# FubarStep_v10thin.net
KiCad netlist of a schematic drawn in EAGLE
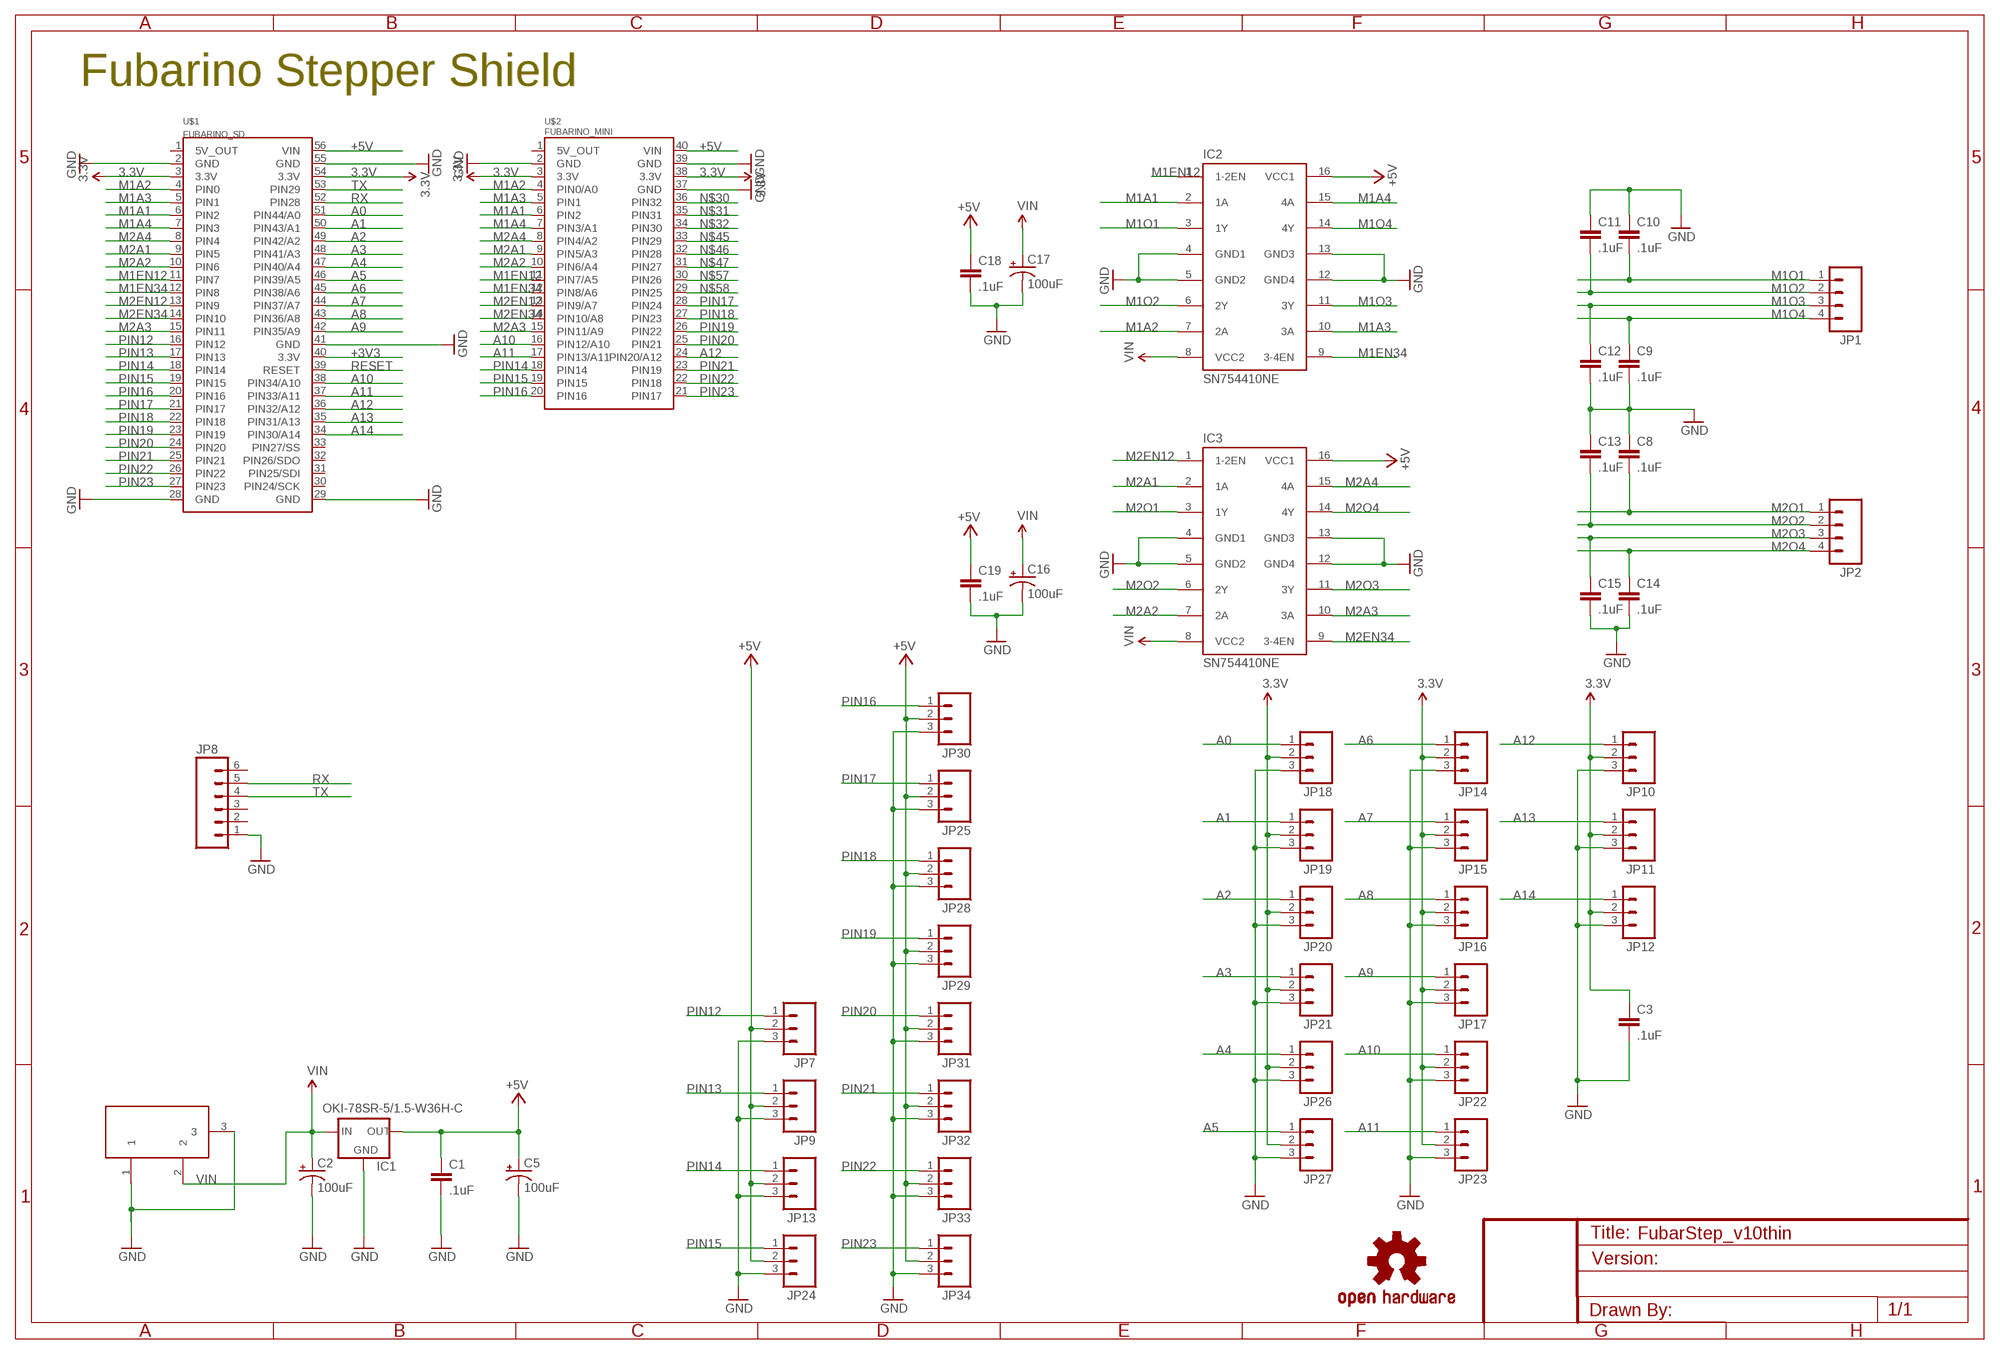
[diagram p0: schematic, sheet 1]

(export (version "E")
  (design (tool "Eeschema 10.0.6"))
  (components
    (comp (ref "C1")
      (value ".1uF")
      (footprint "eagle-import:CAP-PTH-SMALL")
      (libsource (lib "eagle-import") (part "CAPPTH"))
    )
    (comp (ref "C2")
      (value "100uF")
      (footprint "eagle-import:CPOL-RADIAL-100UF-25V")
      (libsource (lib "eagle-import") (part "CAP_POLPTH1"))
    )
    (comp (ref "C3")
      (value ".1uF")
      (footprint "eagle-import:CAP-PTH-SMALL")
      (libsource (lib "eagle-import") (part "CAPPTH"))
    )
    (comp (ref "C5")
      (value "100uF")
      (footprint "eagle-import:CPOL-RADIAL-100UF-25V")
      (libsource (lib "eagle-import") (part "CAP_POLPTH1"))
    )
    (comp (ref "C8")
      (value ".1uF")
      (footprint "eagle-import:CAP-PTH-SMALL")
      (libsource (lib "eagle-import") (part "CAPPTH"))
    )
    (comp (ref "C9")
      (value ".1uF")
      (footprint "eagle-import:CAP-PTH-SMALL")
      (libsource (lib "eagle-import") (part "CAPPTH"))
    )
    (comp (ref "C10")
      (value ".1uF")
      (footprint "eagle-import:CAP-PTH-SMALL")
      (libsource (lib "eagle-import") (part "CAPPTH"))
    )
    (comp (ref "C11")
      (value ".1uF")
      (footprint "eagle-import:CAP-PTH-SMALL")
      (libsource (lib "eagle-import") (part "CAPPTH"))
    )
    (comp (ref "C12")
      (value ".1uF")
      (footprint "eagle-import:CAP-PTH-SMALL")
      (libsource (lib "eagle-import") (part "CAPPTH"))
    )
    (comp (ref "C13")
      (value ".1uF")
      (footprint "eagle-import:CAP-PTH-SMALL")
      (libsource (lib "eagle-import") (part "CAPPTH"))
    )
    (comp (ref "C14")
      (value ".1uF")
      (footprint "eagle-import:CAP-PTH-SMALL")
      (libsource (lib "eagle-import") (part "CAPPTH"))
    )
    (comp (ref "C15")
      (value ".1uF")
      (footprint "eagle-import:CAP-PTH-SMALL")
      (libsource (lib "eagle-import") (part "CAPPTH"))
    )
    (comp (ref "C16")
      (value "100uF")
      (footprint "eagle-import:CPOL-RADIAL-100UF-25V")
      (libsource (lib "eagle-import") (part "CAP_POLPTH1"))
    )
    (comp (ref "C17")
      (value "100uF")
      (footprint "eagle-import:CPOL-RADIAL-100UF-25V")
      (libsource (lib "eagle-import") (part "CAP_POLPTH1"))
    )
    (comp (ref "C18")
      (value ".1uF")
      (footprint "eagle-import:CAP-PTH-SMALL")
      (libsource (lib "eagle-import") (part "CAPPTH"))
    )
    (comp (ref "C19")
      (value ".1uF")
      (footprint "eagle-import:CAP-PTH-SMALL")
      (libsource (lib "eagle-import") (part "CAPPTH"))
    )
    (comp (ref "IC1")
      (value "OKI-78SR-5/1.5-W36H-C")
      (footprint "eagle-import:TO220-IGO")
      (libsource (lib "eagle-import") (part "V_REG_78XXSINK"))
    )
    (comp (ref "IC2")
      (value "SN754410NE")
      (footprint "eagle-import:DIL16")
      (fields (field (name "MF") "Arrow Electronics") (field (name "MPN") "L293E"))
      (libsource (lib "eagle-import") (part "L293E"))
    )
    (comp (ref "IC3")
      (value "SN754410NE")
      (footprint "eagle-import:DIL16")
      (fields (field (name "MF") "Arrow Electronics") (field (name "MPN") "L293E"))
      (libsource (lib "eagle-import") (part "L293E"))
    )
    (comp (ref "JP1")
      (value "M04SCREW_LOCK")
      (footprint "eagle-import:SCREWTERMINAL-3.5MM-4_LOCK")
      (libsource (lib "eagle-import") (part "M04SCREW_LOCK"))
    )
    (comp (ref "JP2")
      (value "M04SCREW_LOCK")
      (footprint "eagle-import:SCREWTERMINAL-3.5MM-4_LOCK")
      (libsource (lib "eagle-import") (part "M04SCREW_LOCK"))
    )
    (comp (ref "JP7")
      (value "M03PTH")
      (footprint "eagle-import:1X03")
      (libsource (lib "eagle-import") (part "M03PTH"))
    )
    (comp (ref "JP8")
      (value "M06LOCK")
      (footprint "eagle-import:1X06_LOCK")
      (libsource (lib "eagle-import") (part "M06LOCK"))
    )
    (comp (ref "JP9")
      (value "M03PTH")
      (footprint "eagle-import:1X03")
      (libsource (lib "eagle-import") (part "M03PTH"))
    )
    (comp (ref "JP10")
      (value "M03PTH")
      (footprint "eagle-import:1X03")
      (libsource (lib "eagle-import") (part "M03PTH"))
    )
    (comp (ref "JP11")
      (value "M03PTH")
      (footprint "eagle-import:1X03")
      (libsource (lib "eagle-import") (part "M03PTH"))
    )
    (comp (ref "JP12")
      (value "M03PTH")
      (footprint "eagle-import:1X03")
      (libsource (lib "eagle-import") (part "M03PTH"))
    )
    (comp (ref "JP13")
      (value "M03PTH")
      (footprint "eagle-import:1X03")
      (libsource (lib "eagle-import") (part "M03PTH"))
    )
    (comp (ref "JP14")
      (value "M03PTH")
      (footprint "eagle-import:1X03")
      (libsource (lib "eagle-import") (part "M03PTH"))
    )
    (comp (ref "JP15")
      (value "M03PTH")
      (footprint "eagle-import:1X03")
      (libsource (lib "eagle-import") (part "M03PTH"))
    )
    (comp (ref "JP16")
      (value "M03PTH")
      (footprint "eagle-import:1X03")
      (libsource (lib "eagle-import") (part "M03PTH"))
    )
    (comp (ref "JP17")
      (value "M03PTH")
      (footprint "eagle-import:1X03")
      (libsource (lib "eagle-import") (part "M03PTH"))
    )
    (comp (ref "JP18")
      (value "M03PTH")
      (footprint "eagle-import:1X03")
      (libsource (lib "eagle-import") (part "M03PTH"))
    )
    (comp (ref "JP19")
      (value "M03PTH")
      (footprint "eagle-import:1X03")
      (libsource (lib "eagle-import") (part "M03PTH"))
    )
    (comp (ref "JP20")
      (value "M03PTH")
      (footprint "eagle-import:1X03")
      (libsource (lib "eagle-import") (part "M03PTH"))
    )
    (comp (ref "JP21")
      (value "M03PTH")
      (footprint "eagle-import:1X03")
      (libsource (lib "eagle-import") (part "M03PTH"))
    )
    (comp (ref "JP22")
      (value "M03PTH")
      (footprint "eagle-import:1X03")
      (libsource (lib "eagle-import") (part "M03PTH"))
    )
    (comp (ref "JP23")
      (value "M03PTH")
      (footprint "eagle-import:1X03")
      (libsource (lib "eagle-import") (part "M03PTH"))
    )
    (comp (ref "JP24")
      (value "M03PTH")
      (footprint "eagle-import:1X03")
      (libsource (lib "eagle-import") (part "M03PTH"))
    )
    (comp (ref "JP25")
      (value "M03PTH")
      (footprint "eagle-import:1X03")
      (libsource (lib "eagle-import") (part "M03PTH"))
    )
    (comp (ref "JP26")
      (value "M03PTH")
      (footprint "eagle-import:1X03")
      (libsource (lib "eagle-import") (part "M03PTH"))
    )
    (comp (ref "JP27")
      (value "M03PTH")
      (footprint "eagle-import:1X03")
      (libsource (lib "eagle-import") (part "M03PTH"))
    )
    (comp (ref "JP28")
      (value "M03PTH")
      (footprint "eagle-import:1X03")
      (libsource (lib "eagle-import") (part "M03PTH"))
    )
    (comp (ref "JP29")
      (value "M03PTH")
      (footprint "eagle-import:1X03")
      (libsource (lib "eagle-import") (part "M03PTH"))
    )
    (comp (ref "JP30")
      (value "M03PTH")
      (footprint "eagle-import:1X03")
      (libsource (lib "eagle-import") (part "M03PTH"))
    )
    (comp (ref "JP31")
      (value "M03PTH")
      (footprint "eagle-import:1X03")
      (libsource (lib "eagle-import") (part "M03PTH"))
    )
    (comp (ref "JP32")
      (value "M03PTH")
      (footprint "eagle-import:1X03")
      (libsource (lib "eagle-import") (part "M03PTH"))
    )
    (comp (ref "JP33")
      (value "M03PTH")
      (footprint "eagle-import:1X03")
      (libsource (lib "eagle-import") (part "M03PTH"))
    )
    (comp (ref "JP34")
      (value "M03PTH")
      (footprint "eagle-import:1X03")
      (libsource (lib "eagle-import") (part "M03PTH"))
    )
    (comp (ref "LOGO1")
      (value "OSHW-LOGOM")
      (footprint "eagle-import:OSHW-LOGO-M")
      (libsource (lib "eagle-import") (part "OSHW-LOGOM"))
    )
    (comp (ref "U$1")
      (value "FUBARINO_SD")
      (footprint "eagle-import:FUBARINO_SD")
      (libsource (lib "eagle-import") (part "FUBARINO_SD"))
    )
    (comp (ref "U$2")
      (value "FUBARINO_MINI")
      (footprint "eagle-import:FUBARINO_MINI")
      (libsource (lib "eagle-import") (part "FUBARINO_MINI"))
    )
    (comp (ref "X1")
      (value "DC21MMX")
      (footprint "eagle-import:DC-21MM")
      (libsource (lib "eagle-import") (part "DC21MMX"))
    )
  )
  (nets
    (net (code "1") (name "+5V") (class "Default")
      (node (ref "C1") (pin "1") (pinfunction "1_1") (pintype "passive"))
      (node (ref "C18") (pin "1") (pinfunction "1_1") (pintype "passive"))
      (node (ref "C19") (pin "1") (pinfunction "1_1") (pintype "passive"))
      (node (ref "C5") (pin "1") (pinfunction "+_1") (pintype "passive"))
      (node (ref "IC1") (pin "OUT") (pinfunction "OUT_OUT") (pintype "output"))
      (node (ref "IC2") (pin "16") (pinfunction "VCC1_16") (pintype "power_in"))
      (node (ref "IC3") (pin "16") (pinfunction "VCC1_16") (pintype "power_in"))
      (node (ref "JP13") (pin "2") (pinfunction "2_2") (pintype "passive"))
      (node (ref "JP24") (pin "2") (pinfunction "2_2") (pintype "passive"))
      (node (ref "JP25") (pin "2") (pinfunction "2_2") (pintype "passive"))
      (node (ref "JP28") (pin "2") (pinfunction "2_2") (pintype "passive"))
      (node (ref "JP29") (pin "2") (pinfunction "2_2") (pintype "passive"))
      (node (ref "JP30") (pin "2") (pinfunction "2_2") (pintype "passive"))
      (node (ref "JP31") (pin "2") (pinfunction "2_2") (pintype "passive"))
      (node (ref "JP32") (pin "2") (pinfunction "2_2") (pintype "passive"))
      (node (ref "JP33") (pin "2") (pinfunction "2_2") (pintype "passive"))
      (node (ref "JP34") (pin "2") (pinfunction "2_2") (pintype "passive"))
      (node (ref "JP7") (pin "2") (pinfunction "2_2") (pintype "passive"))
      (node (ref "JP9") (pin "2") (pinfunction "2_2") (pintype "passive"))
      (node (ref "U$1") (pin "56") (pinfunction "VIN_56") (pintype "bidirectional"))
      (node (ref "U$2") (pin "40") (pinfunction "VIN_40") (pintype "bidirectional"))
    )
    (net (code "2") (name "/+3V3") (class "Default")
      (node (ref "U$1") (pin "40") (pinfunction "3.3V_40") (pintype "bidirectional"))
    )
    (net (code "3") (name "/A0") (class "Default")
      (node (ref "JP18") (pin "1") (pinfunction "1_1") (pintype "passive"))
      (node (ref "U$1") (pin "51") (pinfunction "PIN44/A0_51") (pintype "bidirectional"))
    )
    (net (code "4") (name "/A1") (class "Default")
      (node (ref "JP19") (pin "1") (pinfunction "1_1") (pintype "passive"))
      (node (ref "U$1") (pin "50") (pinfunction "PIN43/A1_50") (pintype "bidirectional"))
    )
    (net (code "5") (name "/A2") (class "Default")
      (node (ref "JP20") (pin "1") (pinfunction "1_1") (pintype "passive"))
      (node (ref "U$1") (pin "49") (pinfunction "PIN42/A2_49") (pintype "bidirectional"))
    )
    (net (code "6") (name "/A3") (class "Default")
      (node (ref "JP21") (pin "1") (pinfunction "1_1") (pintype "passive"))
      (node (ref "U$1") (pin "48") (pinfunction "PIN41/A3_48") (pintype "bidirectional"))
    )
    (net (code "7") (name "/A4") (class "Default")
      (node (ref "JP26") (pin "1") (pinfunction "1_1") (pintype "passive"))
      (node (ref "U$1") (pin "47") (pinfunction "PIN40/A4_47") (pintype "bidirectional"))
    )
    (net (code "8") (name "/A5") (class "Default")
      (node (ref "JP27") (pin "1") (pinfunction "1_1") (pintype "passive"))
      (node (ref "U$1") (pin "46") (pinfunction "PIN39/A5_46") (pintype "bidirectional"))
    )
    (net (code "9") (name "/A6") (class "Default")
      (node (ref "JP14") (pin "1") (pinfunction "1_1") (pintype "passive"))
      (node (ref "U$1") (pin "45") (pinfunction "PIN38/A6_45") (pintype "bidirectional"))
    )
    (net (code "10") (name "/A7") (class "Default")
      (node (ref "JP15") (pin "1") (pinfunction "1_1") (pintype "passive"))
      (node (ref "U$1") (pin "44") (pinfunction "PIN37/A7_44") (pintype "bidirectional"))
    )
    (net (code "11") (name "/A8") (class "Default")
      (node (ref "JP16") (pin "1") (pinfunction "1_1") (pintype "passive"))
      (node (ref "U$1") (pin "43") (pinfunction "PIN36/A8_43") (pintype "bidirectional"))
    )
    (net (code "12") (name "/A9") (class "Default")
      (node (ref "JP17") (pin "1") (pinfunction "1_1") (pintype "passive"))
      (node (ref "U$1") (pin "42") (pinfunction "PIN35/A9_42") (pintype "bidirectional"))
    )
    (net (code "13") (name "/A10") (class "Default")
      (node (ref "JP22") (pin "1") (pinfunction "1_1") (pintype "passive"))
      (node (ref "U$1") (pin "38") (pinfunction "PIN34/A10_38") (pintype "bidirectional"))
      (node (ref "U$2") (pin "16") (pinfunction "PIN12/A10_16") (pintype "bidirectional"))
    )
    (net (code "14") (name "/A11") (class "Default")
      (node (ref "JP23") (pin "1") (pinfunction "1_1") (pintype "passive"))
      (node (ref "U$1") (pin "37") (pinfunction "PIN33/A11_37") (pintype "bidirectional"))
      (node (ref "U$2") (pin "17") (pinfunction "PIN13/A11_17") (pintype "bidirectional"))
    )
    (net (code "15") (name "/A12") (class "Default")
      (node (ref "JP10") (pin "1") (pinfunction "1_1") (pintype "passive"))
      (node (ref "U$1") (pin "36") (pinfunction "PIN32/A12_36") (pintype "bidirectional"))
      (node (ref "U$2") (pin "24") (pinfunction "PIN20/A12_24") (pintype "bidirectional"))
    )
    (net (code "16") (name "/A13") (class "Default")
      (node (ref "JP11") (pin "1") (pinfunction "1_1") (pintype "passive"))
      (node (ref "U$1") (pin "35") (pinfunction "PIN31/A13_35") (pintype "bidirectional"))
    )
    (net (code "17") (name "/A14") (class "Default")
      (node (ref "JP12") (pin "1") (pinfunction "1_1") (pintype "passive"))
      (node (ref "U$1") (pin "34") (pinfunction "PIN30/A14_34") (pintype "bidirectional"))
    )
    (net (code "18") (name "/M1A1") (class "Default")
      (node (ref "IC2") (pin "2") (pinfunction "1A_2") (pintype "input"))
      (node (ref "U$1") (pin "6") (pinfunction "PIN2_6") (pintype "bidirectional"))
      (node (ref "U$2") (pin "6") (pinfunction "PIN2_6") (pintype "bidirectional"))
    )
    (net (code "19") (name "/M1A2") (class "Default")
      (node (ref "IC2") (pin "7") (pinfunction "2A_7") (pintype "input"))
      (node (ref "U$1") (pin "4") (pinfunction "PIN0_4") (pintype "bidirectional"))
      (node (ref "U$2") (pin "4") (pinfunction "PIN0/A0_4") (pintype "bidirectional"))
    )
    (net (code "20") (name "/M1A3") (class "Default")
      (node (ref "IC2") (pin "10") (pinfunction "3A_10") (pintype "input"))
      (node (ref "U$1") (pin "5") (pinfunction "PIN1_5") (pintype "bidirectional"))
      (node (ref "U$2") (pin "5") (pinfunction "PIN1_5") (pintype "bidirectional"))
    )
    (net (code "21") (name "/M1A4") (class "Default")
      (node (ref "IC2") (pin "15") (pinfunction "4A_15") (pintype "input"))
      (node (ref "U$1") (pin "7") (pinfunction "PIN3_7") (pintype "bidirectional"))
      (node (ref "U$2") (pin "7") (pinfunction "PIN3/A1_7") (pintype "bidirectional"))
    )
    (net (code "22") (name "/M1EN12") (class "Default")
      (node (ref "IC2") (pin "1") (pinfunction "1-2EN_1") (pintype "input"))
      (node (ref "U$1") (pin "11") (pinfunction "PIN7_11") (pintype "bidirectional"))
      (node (ref "U$2") (pin "11") (pinfunction "PIN7/A5_11") (pintype "bidirectional"))
    )
    (net (code "23") (name "/M1EN34") (class "Default")
      (node (ref "IC2") (pin "9") (pinfunction "3-4EN_9") (pintype "input"))
      (node (ref "U$1") (pin "12") (pinfunction "PIN8_12") (pintype "bidirectional"))
      (node (ref "U$2") (pin "12") (pinfunction "PIN8/A6_12") (pintype "bidirectional"))
    )
    (net (code "24") (name "/M1O1") (class "Default")
      (node (ref "C10") (pin "2") (pinfunction "2_2") (pintype "passive"))
      (node (ref "IC2") (pin "3") (pinfunction "1Y_3") (pintype "output"))
      (node (ref "JP1") (pin "1") (pinfunction "1_1") (pintype "passive"))
    )
    (net (code "25") (name "/M1O2") (class "Default")
      (node (ref "C11") (pin "2") (pinfunction "2_2") (pintype "passive"))
      (node (ref "IC2") (pin "6") (pinfunction "2Y_6") (pintype "output"))
      (node (ref "JP1") (pin "2") (pinfunction "2_2") (pintype "passive"))
    )
    (net (code "26") (name "/M1O3") (class "Default")
      (node (ref "C12") (pin "1") (pinfunction "1_1") (pintype "passive"))
      (node (ref "IC2") (pin "11") (pinfunction "3Y_11") (pintype "output"))
      (node (ref "JP1") (pin "3") (pinfunction "3_3") (pintype "passive"))
    )
    (net (code "27") (name "/M1O4") (class "Default")
      (node (ref "C9") (pin "1") (pinfunction "1_1") (pintype "passive"))
      (node (ref "IC2") (pin "14") (pinfunction "4Y_14") (pintype "output"))
      (node (ref "JP1") (pin "4") (pinfunction "4_4") (pintype "passive"))
    )
    (net (code "28") (name "/M2A1") (class "Default")
      (node (ref "IC3") (pin "2") (pinfunction "1A_2") (pintype "input"))
      (node (ref "U$1") (pin "9") (pinfunction "PIN5_9") (pintype "bidirectional"))
      (node (ref "U$2") (pin "9") (pinfunction "PIN5/A3_9") (pintype "bidirectional"))
    )
    (net (code "29") (name "/M2A2") (class "Default")
      (node (ref "IC3") (pin "7") (pinfunction "2A_7") (pintype "input"))
      (node (ref "U$1") (pin "10") (pinfunction "PIN6_10") (pintype "bidirectional"))
      (node (ref "U$2") (pin "10") (pinfunction "PIN6/A4_10") (pintype "bidirectional"))
    )
    (net (code "30") (name "/M2A3") (class "Default")
      (node (ref "IC3") (pin "10") (pinfunction "3A_10") (pintype "input"))
      (node (ref "U$1") (pin "15") (pinfunction "PIN11_15") (pintype "bidirectional"))
      (node (ref "U$2") (pin "15") (pinfunction "PIN11/A9_15") (pintype "bidirectional"))
    )
    (net (code "31") (name "/M2A4") (class "Default")
      (node (ref "IC3") (pin "15") (pinfunction "4A_15") (pintype "input"))
      (node (ref "U$1") (pin "8") (pinfunction "PIN4_8") (pintype "bidirectional"))
      (node (ref "U$2") (pin "8") (pinfunction "PIN4/A2_8") (pintype "bidirectional"))
    )
    (net (code "32") (name "/M2EN12") (class "Default")
      (node (ref "IC3") (pin "1") (pinfunction "1-2EN_1") (pintype "input"))
      (node (ref "U$1") (pin "13") (pinfunction "PIN9_13") (pintype "bidirectional"))
      (node (ref "U$2") (pin "13") (pinfunction "PIN9/A7_13") (pintype "bidirectional"))
    )
    (net (code "33") (name "/M2EN34") (class "Default")
      (node (ref "IC3") (pin "9") (pinfunction "3-4EN_9") (pintype "input"))
      (node (ref "U$1") (pin "14") (pinfunction "PIN10_14") (pintype "bidirectional"))
      (node (ref "U$2") (pin "14") (pinfunction "PIN10/A8_14") (pintype "bidirectional"))
    )
    (net (code "34") (name "/M2O1") (class "Default")
      (node (ref "C8") (pin "2") (pinfunction "2_2") (pintype "passive"))
      (node (ref "IC3") (pin "3") (pinfunction "1Y_3") (pintype "output"))
      (node (ref "JP2") (pin "1") (pinfunction "1_1") (pintype "passive"))
    )
    (net (code "35") (name "/M2O2") (class "Default")
      (node (ref "C13") (pin "2") (pinfunction "2_2") (pintype "passive"))
      (node (ref "IC3") (pin "6") (pinfunction "2Y_6") (pintype "output"))
      (node (ref "JP2") (pin "2") (pinfunction "2_2") (pintype "passive"))
    )
    (net (code "36") (name "/M2O3") (class "Default")
      (node (ref "C15") (pin "1") (pinfunction "1_1") (pintype "passive"))
      (node (ref "IC3") (pin "11") (pinfunction "3Y_11") (pintype "output"))
      (node (ref "JP2") (pin "3") (pinfunction "3_3") (pintype "passive"))
    )
    (net (code "37") (name "/M2O4") (class "Default")
      (node (ref "C14") (pin "1") (pinfunction "1_1") (pintype "passive"))
      (node (ref "IC3") (pin "14") (pinfunction "4Y_14") (pintype "output"))
      (node (ref "JP2") (pin "4") (pinfunction "4_4") (pintype "passive"))
    )
    (net (code "38") (name "/N$30") (class "Default")
      (node (ref "U$2") (pin "36") (pinfunction "PIN32_36") (pintype "bidirectional"))
    )
    (net (code "39") (name "/N$31") (class "Default")
      (node (ref "U$2") (pin "35") (pinfunction "PIN31_35") (pintype "bidirectional"))
    )
    (net (code "40") (name "/N$32") (class "Default")
      (node (ref "U$2") (pin "34") (pinfunction "PIN30_34") (pintype "bidirectional"))
    )
    (net (code "41") (name "/N$45") (class "Default")
      (node (ref "U$2") (pin "33") (pinfunction "PIN29_33") (pintype "bidirectional"))
    )
    (net (code "42") (name "/N$46") (class "Default")
      (node (ref "U$2") (pin "32") (pinfunction "PIN28_32") (pintype "bidirectional"))
    )
    (net (code "43") (name "/N$47") (class "Default")
      (node (ref "U$2") (pin "31") (pinfunction "PIN27_31") (pintype "bidirectional"))
    )
    (net (code "44") (name "/N$57") (class "Default")
      (node (ref "U$2") (pin "30") (pinfunction "PIN26_30") (pintype "bidirectional"))
    )
    (net (code "45") (name "/N$58") (class "Default")
      (node (ref "U$2") (pin "29") (pinfunction "PIN25_29") (pintype "bidirectional"))
    )
    (net (code "46") (name "/PIN12") (class "Default")
      (node (ref "JP7") (pin "1") (pinfunction "1_1") (pintype "passive"))
      (node (ref "U$1") (pin "16") (pinfunction "PIN12_16") (pintype "bidirectional"))
    )
    (net (code "47") (name "/PIN13") (class "Default")
      (node (ref "JP9") (pin "1") (pinfunction "1_1") (pintype "passive"))
      (node (ref "U$1") (pin "17") (pinfunction "PIN13_17") (pintype "bidirectional"))
    )
    (net (code "48") (name "/PIN14") (class "Default")
      (node (ref "JP13") (pin "1") (pinfunction "1_1") (pintype "passive"))
      (node (ref "U$1") (pin "18") (pinfunction "PIN14_18") (pintype "bidirectional"))
      (node (ref "U$2") (pin "18") (pinfunction "PIN14_18") (pintype "bidirectional"))
    )
    (net (code "49") (name "/PIN15") (class "Default")
      (node (ref "JP24") (pin "1") (pinfunction "1_1") (pintype "passive"))
      (node (ref "U$1") (pin "19") (pinfunction "PIN15_19") (pintype "bidirectional"))
      (node (ref "U$2") (pin "19") (pinfunction "PIN15_19") (pintype "bidirectional"))
    )
    (net (code "50") (name "/PIN16") (class "Default")
      (node (ref "JP30") (pin "1") (pinfunction "1_1") (pintype "passive"))
      (node (ref "U$1") (pin "20") (pinfunction "PIN16_20") (pintype "bidirectional"))
      (node (ref "U$2") (pin "20") (pinfunction "PIN16_20") (pintype "bidirectional"))
    )
    (net (code "51") (name "/PIN17") (class "Default")
      (node (ref "JP25") (pin "1") (pinfunction "1_1") (pintype "passive"))
      (node (ref "U$1") (pin "21") (pinfunction "PIN17_21") (pintype "bidirectional"))
      (node (ref "U$2") (pin "28") (pinfunction "PIN24_28") (pintype "bidirectional"))
    )
    (net (code "52") (name "/PIN18") (class "Default")
      (node (ref "JP28") (pin "1") (pinfunction "1_1") (pintype "passive"))
      (node (ref "U$1") (pin "22") (pinfunction "PIN18_22") (pintype "bidirectional"))
      (node (ref "U$2") (pin "27") (pinfunction "PIN23_27") (pintype "bidirectional"))
    )
    (net (code "53") (name "/PIN19") (class "Default")
      (node (ref "JP29") (pin "1") (pinfunction "1_1") (pintype "passive"))
      (node (ref "U$1") (pin "23") (pinfunction "PIN19_23") (pintype "bidirectional"))
      (node (ref "U$2") (pin "26") (pinfunction "PIN22_26") (pintype "bidirectional"))
    )
    (net (code "54") (name "/PIN20") (class "Default")
      (node (ref "JP31") (pin "1") (pinfunction "1_1") (pintype "passive"))
      (node (ref "U$1") (pin "24") (pinfunction "PIN20_24") (pintype "bidirectional"))
      (node (ref "U$2") (pin "25") (pinfunction "PIN21_25") (pintype "bidirectional"))
    )
    (net (code "55") (name "/PIN21") (class "Default")
      (node (ref "JP32") (pin "1") (pinfunction "1_1") (pintype "passive"))
      (node (ref "U$1") (pin "25") (pinfunction "PIN21_25") (pintype "bidirectional"))
      (node (ref "U$2") (pin "23") (pinfunction "PIN19_23") (pintype "bidirectional"))
    )
    (net (code "56") (name "/PIN22") (class "Default")
      (node (ref "JP33") (pin "1") (pinfunction "1_1") (pintype "passive"))
      (node (ref "U$1") (pin "26") (pinfunction "PIN22_26") (pintype "bidirectional"))
      (node (ref "U$2") (pin "22") (pinfunction "PIN18_22") (pintype "bidirectional"))
    )
    (net (code "57") (name "/PIN23") (class "Default")
      (node (ref "JP34") (pin "1") (pinfunction "1_1") (pintype "passive"))
      (node (ref "U$1") (pin "27") (pinfunction "PIN23_27") (pintype "bidirectional"))
      (node (ref "U$2") (pin "21") (pinfunction "PIN17_21") (pintype "bidirectional"))
    )
    (net (code "58") (name "/RESET") (class "Default")
      (node (ref "U$1") (pin "39") (pinfunction "RESET_39") (pintype "bidirectional"))
    )
    (net (code "59") (name "/RX") (class "Default")
      (node (ref "JP8") (pin "5") (pinfunction "5_5") (pintype "passive"))
      (node (ref "U$1") (pin "52") (pinfunction "PIN28_52") (pintype "bidirectional"))
    )
    (net (code "60") (name "/TX") (class "Default")
      (node (ref "JP8") (pin "4") (pinfunction "4_4") (pintype "passive"))
      (node (ref "U$1") (pin "53") (pinfunction "PIN29_53") (pintype "bidirectional"))
    )
    (net (code "61") (name "3.3V") (class "Default")
      (node (ref "C3") (pin "1") (pinfunction "1_1") (pintype "passive"))
      (node (ref "JP10") (pin "2") (pinfunction "2_2") (pintype "passive"))
      (node (ref "JP11") (pin "2") (pinfunction "2_2") (pintype "passive"))
      (node (ref "JP12") (pin "2") (pinfunction "2_2") (pintype "passive"))
      (node (ref "JP14") (pin "2") (pinfunction "2_2") (pintype "passive"))
      (node (ref "JP15") (pin "2") (pinfunction "2_2") (pintype "passive"))
      (node (ref "JP16") (pin "2") (pinfunction "2_2") (pintype "passive"))
      (node (ref "JP17") (pin "2") (pinfunction "2_2") (pintype "passive"))
      (node (ref "JP18") (pin "2") (pinfunction "2_2") (pintype "passive"))
      (node (ref "JP19") (pin "2") (pinfunction "2_2") (pintype "passive"))
      (node (ref "JP20") (pin "2") (pinfunction "2_2") (pintype "passive"))
      (node (ref "JP21") (pin "2") (pinfunction "2_2") (pintype "passive"))
      (node (ref "JP22") (pin "2") (pinfunction "2_2") (pintype "passive"))
      (node (ref "JP23") (pin "2") (pinfunction "2_2") (pintype "passive"))
      (node (ref "JP26") (pin "2") (pinfunction "2_2") (pintype "passive"))
      (node (ref "JP27") (pin "2") (pinfunction "2_2") (pintype "passive"))
      (node (ref "U$1") (pin "3") (pinfunction "3.3V_3") (pintype "bidirectional"))
      (node (ref "U$1") (pin "54") (pinfunction "3.3V_54") (pintype "bidirectional"))
      (node (ref "U$2") (pin "3") (pinfunction "3.3V_3") (pintype "bidirectional"))
      (node (ref "U$2") (pin "38") (pinfunction "3.3V_38") (pintype "bidirectional"))
    )
    (net (code "62") (name "GND") (class "Default")
      (node (ref "C1") (pin "2") (pinfunction "2_2") (pintype "passive"))
      (node (ref "C10") (pin "1") (pinfunction "1_1") (pintype "passive"))
      (node (ref "C11") (pin "1") (pinfunction "1_1") (pintype "passive"))
      (node (ref "C12") (pin "2") (pinfunction "2_2") (pintype "passive"))
      (node (ref "C13") (pin "1") (pinfunction "1_1") (pintype "passive"))
      (node (ref "C14") (pin "2") (pinfunction "2_2") (pintype "passive"))
      (node (ref "C15") (pin "2") (pinfunction "2_2") (pintype "passive"))
      (node (ref "C16") (pin "2") (pinfunction "-_2") (pintype "passive"))
      (node (ref "C17") (pin "2") (pinfunction "-_2") (pintype "passive"))
      (node (ref "C18") (pin "2") (pinfunction "2_2") (pintype "passive"))
      (node (ref "C19") (pin "2") (pinfunction "2_2") (pintype "passive"))
      (node (ref "C2") (pin "2") (pinfunction "-_2") (pintype "passive"))
      (node (ref "C3") (pin "2") (pinfunction "2_2") (pintype "passive"))
      (node (ref "C5") (pin "2") (pinfunction "-_2") (pintype "passive"))
      (node (ref "C8") (pin "1") (pinfunction "1_1") (pintype "passive"))
      (node (ref "C9") (pin "2") (pinfunction "2_2") (pintype "passive"))
      (node (ref "IC1") (pin "GND") (pinfunction "GND_GND") (pintype "input"))
      (node (ref "IC2") (pin "12") (pinfunction "GND4_12") (pintype "power_in"))
      (node (ref "IC2") (pin "13") (pinfunction "GND3_13") (pintype "power_in"))
      (node (ref "IC2") (pin "4") (pinfunction "GND1_4") (pintype "power_in"))
      (node (ref "IC2") (pin "5") (pinfunction "GND2_5") (pintype "power_in"))
      (node (ref "IC3") (pin "12") (pinfunction "GND4_12") (pintype "power_in"))
      (node (ref "IC3") (pin "13") (pinfunction "GND3_13") (pintype "power_in"))
      (node (ref "IC3") (pin "4") (pinfunction "GND1_4") (pintype "power_in"))
      (node (ref "IC3") (pin "5") (pinfunction "GND2_5") (pintype "power_in"))
      (node (ref "JP10") (pin "3") (pinfunction "3_3") (pintype "passive"))
      (node (ref "JP11") (pin "3") (pinfunction "3_3") (pintype "passive"))
      (node (ref "JP12") (pin "3") (pinfunction "3_3") (pintype "passive"))
      (node (ref "JP13") (pin "3") (pinfunction "3_3") (pintype "passive"))
      (node (ref "JP14") (pin "3") (pinfunction "3_3") (pintype "passive"))
      (node (ref "JP15") (pin "3") (pinfunction "3_3") (pintype "passive"))
      (node (ref "JP16") (pin "3") (pinfunction "3_3") (pintype "passive"))
      (node (ref "JP17") (pin "3") (pinfunction "3_3") (pintype "passive"))
      (node (ref "JP18") (pin "3") (pinfunction "3_3") (pintype "passive"))
      (node (ref "JP19") (pin "3") (pinfunction "3_3") (pintype "passive"))
      (node (ref "JP20") (pin "3") (pinfunction "3_3") (pintype "passive"))
      (node (ref "JP21") (pin "3") (pinfunction "3_3") (pintype "passive"))
      (node (ref "JP22") (pin "3") (pinfunction "3_3") (pintype "passive"))
      (node (ref "JP23") (pin "3") (pinfunction "3_3") (pintype "passive"))
      (node (ref "JP24") (pin "3") (pinfunction "3_3") (pintype "passive"))
      (node (ref "JP25") (pin "3") (pinfunction "3_3") (pintype "passive"))
      (node (ref "JP26") (pin "3") (pinfunction "3_3") (pintype "passive"))
      (node (ref "JP27") (pin "3") (pinfunction "3_3") (pintype "passive"))
      (node (ref "JP28") (pin "3") (pinfunction "3_3") (pintype "passive"))
      (node (ref "JP29") (pin "3") (pinfunction "3_3") (pintype "passive"))
      (node (ref "JP30") (pin "3") (pinfunction "3_3") (pintype "passive"))
      (node (ref "JP31") (pin "3") (pinfunction "3_3") (pintype "passive"))
      (node (ref "JP32") (pin "3") (pinfunction "3_3") (pintype "passive"))
      (node (ref "JP33") (pin "3") (pinfunction "3_3") (pintype "passive"))
      (node (ref "JP34") (pin "3") (pinfunction "3_3") (pintype "passive"))
      (node (ref "JP7") (pin "3") (pinfunction "3_3") (pintype "passive"))
      (node (ref "JP8") (pin "1") (pinfunction "1_1") (pintype "passive"))
      (node (ref "JP9") (pin "3") (pinfunction "3_3") (pintype "passive"))
      (node (ref "U$1") (pin "2") (pinfunction "GND_2") (pintype "bidirectional"))
      (node (ref "U$1") (pin "28") (pinfunction "GND_28") (pintype "bidirectional"))
      (node (ref "U$1") (pin "29") (pinfunction "GND_29") (pintype "bidirectional"))
      (node (ref "U$1") (pin "41") (pinfunction "GND_41") (pintype "bidirectional"))
      (node (ref "U$1") (pin "55") (pinfunction "GND_55") (pintype "bidirectional"))
      (node (ref "U$2") (pin "2") (pinfunction "GND_2") (pintype "bidirectional"))
      (node (ref "U$2") (pin "37") (pinfunction "GND_37") (pintype "bidirectional"))
      (node (ref "U$2") (pin "39") (pinfunction "GND_39") (pintype "bidirectional"))
      (node (ref "X1") (pin "1") (pinfunction "1_1") (pintype "power_in"))
      (node (ref "X1") (pin "3") (pinfunction "3_3") (pintype "power_in"))
    )
    (net (code "63") (name "VIN") (class "Default")
      (node (ref "C16") (pin "1") (pinfunction "+_1") (pintype "passive"))
      (node (ref "C17") (pin "1") (pinfunction "+_1") (pintype "passive"))
      (node (ref "C2") (pin "1") (pinfunction "+_1") (pintype "passive"))
      (node (ref "IC1") (pin "IN") (pinfunction "IN_IN") (pintype "input"))
      (node (ref "IC2") (pin "8") (pinfunction "VCC2_8") (pintype "power_in"))
      (node (ref "IC3") (pin "8") (pinfunction "VCC2_8") (pintype "power_in"))
      (node (ref "X1") (pin "2") (pinfunction "2_2") (pintype "power_in"))
    )
    (net (code "64") (name "unconnected-(JP8-Pad2)") (class "Default")
      (node (ref "JP8") (pin "2") (pinfunction "2_2") (pintype "passive"))
    )
    (net (code "65") (name "unconnected-(JP8-Pad3)") (class "Default")
      (node (ref "JP8") (pin "3") (pinfunction "3_3") (pintype "passive"))
    )
    (net (code "66") (name "unconnected-(JP8-Pad6)") (class "Default")
      (node (ref "JP8") (pin "6") (pinfunction "6_6") (pintype "passive"))
    )
    (net (code "67") (name "unconnected-(U$1-5V_OUT-Pad1)") (class "Default")
      (node (ref "U$1") (pin "1") (pinfunction "5V_OUT_1") (pintype "bidirectional"))
    )
    (net (code "68") (name "unconnected-(U$1-PIN24{slash}SCK-Pad30)") (class "Default")
      (node (ref "U$1") (pin "30") (pinfunction "PIN24/SCK_30") (pintype "bidirectional"))
    )
    (net (code "69") (name "unconnected-(U$1-PIN25{slash}SDI-Pad31)") (class "Default")
      (node (ref "U$1") (pin "31") (pinfunction "PIN25/SDI_31") (pintype "bidirectional"))
    )
    (net (code "70") (name "unconnected-(U$1-PIN26{slash}SDO-Pad32)") (class "Default")
      (node (ref "U$1") (pin "32") (pinfunction "PIN26/SDO_32") (pintype "bidirectional"))
    )
    (net (code "71") (name "unconnected-(U$1-PIN27{slash}SS-Pad33)") (class "Default")
      (node (ref "U$1") (pin "33") (pinfunction "PIN27/SS_33") (pintype "bidirectional"))
    )
    (net (code "72") (name "unconnected-(U$2-5V_OUT-Pad1)") (class "Default")
      (node (ref "U$2") (pin "1") (pinfunction "5V_OUT_1") (pintype "bidirectional"))
    )
  )
)
